# pc_OpenOx-ESP32_v1_1.net
KiCad netlist of a schematic drawn in EAGLE
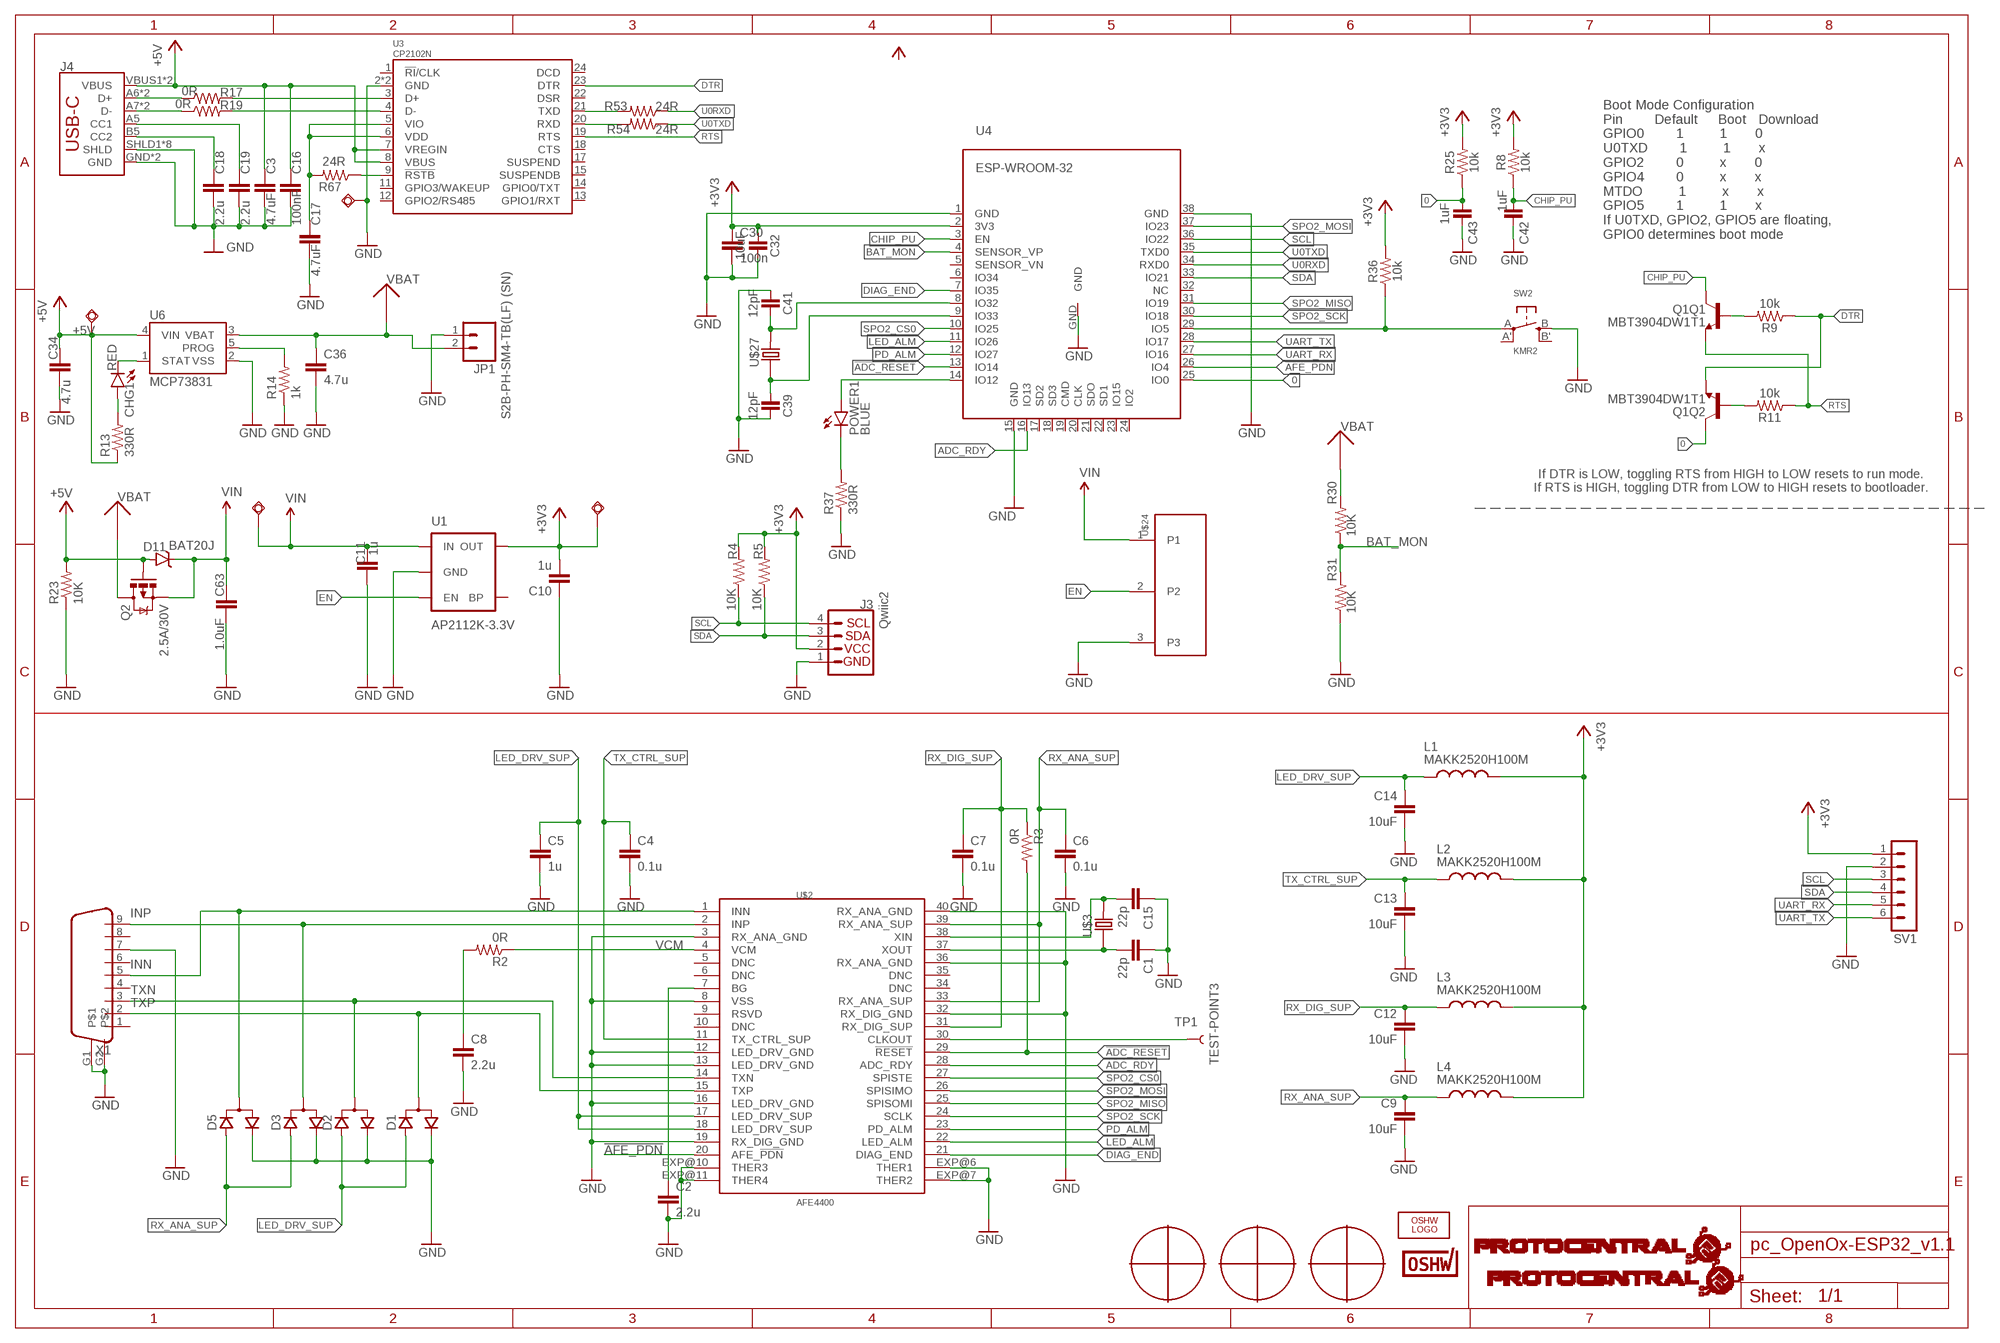
[diagram p0: schematic, sheet 1]

(export (version "E")
  (design (tool "Eeschema 10.0.6"))
  (components
    (comp (ref "C1")
      (value "22p")
      (footprint "eagle-import:C0402")
      (libsource (lib "eagle-import") (part "C-EUC0402"))
    )
    (comp (ref "C2")
      (value "2.2u")
      (footprint "eagle-import:C0402")
      (libsource (lib "eagle-import") (part "C-EUC0402"))
    )
    (comp (ref "C3")
      (value "4.7uF")
      (footprint "eagle-import:C0402")
      (libsource (lib "eagle-import") (part "C-EUC0402"))
    )
    (comp (ref "C4")
      (value "0.1u")
      (footprint "eagle-import:C0805")
      (libsource (lib "eagle-import") (part "C-EUC0805"))
    )
    (comp (ref "C5")
      (value "1u")
      (footprint "eagle-import:C0805")
      (libsource (lib "eagle-import") (part "C-EUC0805"))
    )
    (comp (ref "C6")
      (value "0.1u")
      (footprint "eagle-import:C0805")
      (libsource (lib "eagle-import") (part "C-EUC0805"))
    )
    (comp (ref "C7")
      (value "0.1u")
      (footprint "eagle-import:C0805")
      (libsource (lib "eagle-import") (part "C-EUC0805"))
    )
    (comp (ref "C8")
      (value "2.2u")
      (footprint "eagle-import:C0402")
      (libsource (lib "eagle-import") (part "C-EUC0402"))
    )
    (comp (ref "C9")
      (value "10uF")
      (footprint "eagle-import:C0805")
      (libsource (lib "eagle-import") (part "C-EUC0805"))
    )
    (comp (ref "C10")
      (value "1u")
      (footprint "eagle-import:C0805")
      (libsource (lib "eagle-import") (part "C-EUC0805"))
    )
    (comp (ref "C11")
      (value "1u")
      (footprint "eagle-import:C0805")
      (libsource (lib "eagle-import") (part "C-EUC0805"))
    )
    (comp (ref "C12")
      (value "10uF")
      (footprint "eagle-import:C0805")
      (libsource (lib "eagle-import") (part "C-EUC0805"))
    )
    (comp (ref "C13")
      (value "10uF")
      (footprint "eagle-import:C0805")
      (libsource (lib "eagle-import") (part "C-EUC0805"))
    )
    (comp (ref "C14")
      (value "10uF")
      (footprint "eagle-import:C0805")
      (libsource (lib "eagle-import") (part "C-EUC0805"))
    )
    (comp (ref "C15")
      (value "22p")
      (footprint "eagle-import:C0402")
      (libsource (lib "eagle-import") (part "C-EUC0402"))
    )
    (comp (ref "C16")
      (value "100nF")
      (footprint "eagle-import:C0402")
      (libsource (lib "eagle-import") (part "C-EUC0402"))
    )
    (comp (ref "C17")
      (value "4.7uF")
      (footprint "eagle-import:C0402")
      (libsource (lib "eagle-import") (part "C-EUC0402"))
    )
    (comp (ref "C18")
      (value "2.2u")
      (footprint "eagle-import:C0402")
      (libsource (lib "eagle-import") (part "C-EUC0402"))
    )
    (comp (ref "C19")
      (value "2.2u")
      (footprint "eagle-import:C0402")
      (libsource (lib "eagle-import") (part "C-EUC0402"))
    )
    (comp (ref "C30")
      (value "100n")
      (footprint "eagle-import:C0805")
      (libsource (lib "eagle-import") (part "C-EUC0805"))
    )
    (comp (ref "C32")
      (value "10uF")
      (footprint "eagle-import:C0805")
      (libsource (lib "eagle-import") (part "CAPACITORS-0805"))
    )
    (comp (ref "C34")
      (value "4.7u")
      (footprint "eagle-import:C0805")
      (libsource (lib "eagle-import") (part "C-EUC0805"))
    )
    (comp (ref "C36")
      (value "4.7u")
      (footprint "eagle-import:C0805")
      (libsource (lib "eagle-import") (part "C-EUC0805"))
    )
    (comp (ref "C39")
      (value "12pF")
      (footprint "eagle-import:C0402")
      (libsource (lib "eagle-import") (part "CAPACITORS-0402"))
    )
    (comp (ref "C41")
      (value "12pF")
      (footprint "eagle-import:C0402")
      (libsource (lib "eagle-import") (part "CAPACITORS-0402"))
    )
    (comp (ref "C42")
      (value "1uF")
      (footprint "eagle-import:C0402")
      (libsource (lib "eagle-import") (part "CAPACITORS-0402"))
    )
    (comp (ref "C43")
      (value "1uF")
      (footprint "eagle-import:C0402")
      (libsource (lib "eagle-import") (part "CAPACITORS-0402"))
    )
    (comp (ref "C63")
      (value "1.0uF")
      (footprint "eagle-import:C0402")
      (libsource (lib "eagle-import") (part "C-EUC0402"))
    )
    (comp (ref "CHG1")
      (value "RED")
      (footprint "eagle-import:CHIPLED_0603")
      (libsource (lib "eagle-import") (part "LEDCHIPLED_0603"))
    )
    (comp (ref "D1")
      (value "D_ACACSOT323")
      (footprint "eagle-import:SOT323")
      (libsource (lib "eagle-import") (part "D_ACACSOT323"))
    )
    (comp (ref "D2")
      (value "D_ACACSOT323")
      (footprint "eagle-import:SOT323")
      (libsource (lib "eagle-import") (part "D_ACACSOT323"))
    )
    (comp (ref "D3")
      (value "D_ACACSOT323")
      (footprint "eagle-import:SOT323")
      (libsource (lib "eagle-import") (part "D_ACACSOT323"))
    )
    (comp (ref "D5")
      (value "D_ACACSOT323")
      (footprint "eagle-import:SOT323")
      (libsource (lib "eagle-import") (part "D_ACACSOT323"))
    )
    (comp (ref "D11")
      (value "BAT20J")
      (footprint "eagle-import:SOD-323")
      (libsource (lib "eagle-import") (part "DIODE-SCHOTTKY-BAT20J"))
    )
    (comp (ref "J3")
      (value "Qwiic2")
      (footprint "eagle-import:1X04_1MM_RA")
      (libsource (lib "eagle-import") (part "QWIIC_CONNECTORJS-1MM"))
    )
    (comp (ref "J4")
      (value "USB_C2-LAYER")
      (footprint "eagle-import:USB-C-16P")
      (libsource (lib "eagle-import") (part "USB_C2-LAYER"))
    )
    (comp (ref "JP1")
      (value "S2B-PH-SM4-TB(LF) (SN)")
      (footprint "eagle-import:JST-2-SMD")
      (libsource (lib "eagle-import") (part "M02-JST-2MM-SMT"))
    )
    (comp (ref "L1")
      (value "MAKK2520H100M")
      (footprint "eagle-import:INDC2520X100N")
      (fields (field (name "MF") "Taiyo Yuden"))
      (libsource (lib "eagle-import") (part "MAKK2520H100M"))
    )
    (comp (ref "L2")
      (value "MAKK2520H100M")
      (footprint "eagle-import:INDC2520X100N")
      (fields (field (name "MF") "Taiyo Yuden"))
      (libsource (lib "eagle-import") (part "MAKK2520H100M"))
    )
    (comp (ref "L3")
      (value "MAKK2520H100M")
      (footprint "eagle-import:INDC2520X100N")
      (fields (field (name "MF") "Taiyo Yuden"))
      (libsource (lib "eagle-import") (part "MAKK2520H100M"))
    )
    (comp (ref "L4")
      (value "MAKK2520H100M")
      (footprint "eagle-import:INDC2520X100N")
      (fields (field (name "MF") "Taiyo Yuden"))
      (libsource (lib "eagle-import") (part "MAKK2520H100M"))
    )
    (comp (ref "LOGO2")
      (value "OSHW_LOGO_FILLX0200-NT")
      (footprint "eagle-import:OSHW_FILLX200_NOTEXT")
      (libsource (lib "eagle-import") (part "OSHW_LOGO_FILLX0200-NT"))
    )
    (comp (ref "POWER1")
      (value "BLUE")
      (footprint "eagle-import:CHIPLED_0603")
      (libsource (lib "eagle-import") (part "LEDCHIPLED_0603"))
    )
    (comp (ref "Q1")
      (value "MBT3904DW1T1")
      (footprint "eagle-import:SC70-6")
      (libsource (lib "eagle-import") (part "MBT3904DW1T1"))
    )
    (comp (ref "Q2")
      (value "2.5A/30V")
      (footprint "eagle-import:SOT23-3")
      (libsource (lib "eagle-import") (part "MOSFET-PCHANNELDMG2307L"))
    )
    (comp (ref "R2")
      (value "0R")
      (footprint "eagle-import:R0402")
      (libsource (lib "eagle-import") (part "R-US_R0402"))
    )
    (comp (ref "R3")
      (value "0R")
      (footprint "eagle-import:R0805")
      (libsource (lib "eagle-import") (part "R-US_R0805"))
    )
    (comp (ref "R4")
      (value "10K")
      (footprint "eagle-import:R0402")
      (libsource (lib "eagle-import") (part "R-US_R0402"))
    )
    (comp (ref "R5")
      (value "10K")
      (footprint "eagle-import:R0402")
      (libsource (lib "eagle-import") (part "R-US_R0402"))
    )
    (comp (ref "R8")
      (value "10k")
      (footprint "eagle-import:0603")
      (libsource (lib "eagle-import") (part "10KOHM-1/10W-1%(0603)0603"))
    )
    (comp (ref "R9")
      (value "10k")
      (footprint "eagle-import:0603")
      (libsource (lib "eagle-import") (part "10KOHM-0603-1/10W-1%"))
    )
    (comp (ref "R11")
      (value "10k")
      (footprint "eagle-import:0603")
      (libsource (lib "eagle-import") (part "10KOHM-0603-1/10W-1%"))
    )
    (comp (ref "R13")
      (value "330R")
      (footprint "eagle-import:R0402")
      (libsource (lib "eagle-import") (part "R-US_R0402"))
    )
    (comp (ref "R14")
      (value "1k")
      (footprint "eagle-import:R0402")
      (libsource (lib "eagle-import") (part "R-US_R0402"))
    )
    (comp (ref "R17")
      (value "0R")
      (footprint "eagle-import:R0402")
      (libsource (lib "eagle-import") (part "R-US_R0402"))
    )
    (comp (ref "R19")
      (value "0R")
      (footprint "eagle-import:R0402")
      (libsource (lib "eagle-import") (part "R-US_R0402"))
    )
    (comp (ref "R23")
      (value "10K")
      (footprint "eagle-import:R0402")
      (libsource (lib "eagle-import") (part "R-US_R0402"))
    )
    (comp (ref "R25")
      (value "10k")
      (footprint "eagle-import:0603")
      (libsource (lib "eagle-import") (part "10KOHM-1/10W-1%(0603)0603"))
    )
    (comp (ref "R30")
      (value "10K")
      (footprint "eagle-import:R0402")
      (libsource (lib "eagle-import") (part "R-US_R0402"))
    )
    (comp (ref "R31")
      (value "10K")
      (footprint "eagle-import:R0402")
      (libsource (lib "eagle-import") (part "R-US_R0402"))
    )
    (comp (ref "R36")
      (value "10k")
      (footprint "eagle-import:0603")
      (libsource (lib "eagle-import") (part "10KOHM-1/10W-1%(0603)0603"))
    )
    (comp (ref "R37")
      (value "330R")
      (footprint "eagle-import:R0402")
      (libsource (lib "eagle-import") (part "R-US_R0402"))
    )
    (comp (ref "R53")
      (value "24R")
      (footprint "eagle-import:R0402")
      (libsource (lib "eagle-import") (part "R-US_R0402"))
    )
    (comp (ref "R54")
      (value "24R")
      (footprint "eagle-import:R0402")
      (libsource (lib "eagle-import") (part "R-US_R0402"))
    )
    (comp (ref "R67")
      (value "24R")
      (footprint "eagle-import:R0402")
      (libsource (lib "eagle-import") (part "R-US_R0402"))
    )
    (comp (ref "SV1")
      (value "MA06-1")
      (footprint "eagle-import:MA06-1")
      (libsource (lib "eagle-import") (part "MA06-1"))
    )
    (comp (ref "SW2")
      (value "KMR2")
      (footprint "eagle-import:BTN_KMR2_4.6X2.8")
      (libsource (lib "eagle-import") (part "SWITCH_TACT_SMT4.6X2.8"))
    )
    (comp (ref "SWIO1")
      (value "TPSQTP13R")
      (footprint "eagle-import:TP13R")
      (libsource (lib "eagle-import") (part "TPSQTP13R"))
    )
    (comp (ref "SWIO2")
      (value "TPSQTP13R")
      (footprint "eagle-import:TP13R")
      (libsource (lib "eagle-import") (part "TPSQTP13R"))
    )
    (comp (ref "SWIO3")
      (value "TPSQTP13R")
      (footprint "eagle-import:TP13R")
      (libsource (lib "eagle-import") (part "TPSQTP13R"))
    )
    (comp (ref "SWIO17")
      (value "TPSQTP13R")
      (footprint "eagle-import:TP13R")
      (libsource (lib "eagle-import") (part "TPSQTP13R"))
    )
    (comp (ref "TP1")
      (value "TEST-POINT3")
      (footprint "eagle-import:PAD.03X.03")
      (libsource (lib "eagle-import") (part "TEST-POINT3"))
    )
    (comp (ref "U$2")
      (value "AFE4400")
      (footprint "eagle-import:QFN-40")
      (libsource (lib "eagle-import") (part "AFE4400"))
    )
    (comp (ref "U$3")
      (value "ABM3")
      (footprint "eagle-import:ABM3")
      (libsource (lib "eagle-import") (part "ABM3"))
    )
    (comp (ref "U$4")
      (value "PROTY_LOGO_WITH_TEXT")
      (footprint "eagle-import:PROTY_WITH_TEXT")
      (libsource (lib "eagle-import") (part "PROTY_LOGO_WITH_TEXT"))
    )
    (comp (ref "U$5")
      (value "PROTY-LOGO")
      (footprint "eagle-import:LOGO-PROTY")
      (libsource (lib "eagle-import") (part "PROTY-LOGO"))
    )
    (comp (ref "U$7")
      (value "CERT-SMALL")
      (footprint "eagle-import:CERT-SMALL-SILK")
      (libsource (lib "eagle-import") (part "CERT-SMALL"))
    )
    (comp (ref "U$24")
      (value "JS102011SCQN")
      (footprint "eagle-import:JS102011SCQN")
      (libsource (lib "eagle-import") (part "JS102011SCQN"))
    )
    (comp (ref "U$27")
      (value "520-327-12.5-34B(32.768KHZ)")
      (footprint "eagle-import:ECX-31B")
      (libsource (lib "eagle-import") (part "ECS-X-34B"))
    )
    (comp (ref "U$33")
      (value "FUDCIALPOINTS")
      (footprint "eagle-import:FIDUCIALPOINTS")
      (libsource (lib "eagle-import") (part "FUDCIALPOINTS"))
    )
    (comp (ref "U$34")
      (value "FUDCIALPOINTS")
      (footprint "eagle-import:FIDUCIALPOINTS")
      (libsource (lib "eagle-import") (part "FUDCIALPOINTS"))
    )
    (comp (ref "U$35")
      (value "FUDCIALPOINTS")
      (footprint "eagle-import:FIDUCIALPOINTS")
      (libsource (lib "eagle-import") (part "FUDCIALPOINTS"))
    )
    (comp (ref "U1")
      (value "AP2112K-3.3V")
      (footprint "eagle-import:SOT23-5")
      (libsource (lib "eagle-import") (part "V_REG_LDOSMD"))
    )
    (comp (ref "U3")
      (value "CP2102N")
      (footprint "eagle-import:QFN24")
      (libsource (lib "eagle-import") (part "CP2102N"))
    )
    (comp (ref "U4")
      (value "ESP-WROOM-32")
      (footprint "eagle-import:ESP-WROOM-32")
      (libsource (lib "eagle-import") (part "ESP-WROOM-32"))
    )
    (comp (ref "U6")
      (value "MCP73831")
      (footprint "eagle-import:SOT23-5")
      (libsource (lib "eagle-import") (part "MCP73831"))
    )
    (comp (ref "X1")
      (value "DB9")
      (footprint "eagle-import:DB9")
      (libsource (lib "eagle-import") (part "DB9"))
    )
  )
  (nets
    (net (code "1") (name "+3V3") (class "Default")
      (node (ref "C10") (pin "2") (pinfunction "2_2") (pintype "passive"))
      (node (ref "C30") (pin "1") (pinfunction "1_1") (pintype "passive"))
      (node (ref "C32") (pin "1") (pinfunction "1_1") (pintype "passive"))
      (node (ref "J3") (pin "2") (pinfunction "2_2") (pintype "power_in"))
      (node (ref "L1") (pin "2") (pinfunction "2_2") (pintype "passive"))
      (node (ref "L2") (pin "2") (pinfunction "2_2") (pintype "passive"))
      (node (ref "L3") (pin "2") (pinfunction "2_2") (pintype "passive"))
      (node (ref "L4") (pin "2") (pinfunction "2_2") (pintype "passive"))
      (node (ref "R25") (pin "2") (pinfunction "2_2") (pintype "passive"))
      (node (ref "R36") (pin "2") (pinfunction "2_2") (pintype "passive"))
      (node (ref "R4") (pin "2") (pinfunction "2_2") (pintype "passive"))
      (node (ref "R5") (pin "2") (pinfunction "2_2") (pintype "passive"))
      (node (ref "R8") (pin "2") (pinfunction "2_2") (pintype "passive"))
      (node (ref "SV1") (pin "1") (pinfunction "1_1") (pintype "passive"))
      (node (ref "SWIO1") (pin "TP") (pinfunction "TP_TP") (pintype "input"))
      (node (ref "U1") (pin "5") (pinfunction "OUT_5") (pintype "passive"))
      (node (ref "U4") (pin "2") (pinfunction "3V3_2") (pintype "bidirectional"))
    )
    (net (code "2") (name "+5V") (class "Default")
      (node (ref "C16") (pin "1") (pinfunction "1_1") (pintype "passive"))
      (node (ref "C3") (pin "1") (pinfunction "1_1") (pintype "passive"))
      (node (ref "C34") (pin "1") (pinfunction "1_1") (pintype "passive"))
      (node (ref "D11") (pin "A") (pinfunction "A_A") (pintype "passive"))
      (node (ref "J4") (pin "VBUS1") (pinfunction "VBUS_VBUS1") (pintype "bidirectional"))
      (node (ref "J4") (pin "VBUS2") (pinfunction "VBUS_VBUS2") (pintype "bidirectional"))
      (node (ref "Q2") (pin "1") (pinfunction "G_1") (pintype "passive"))
      (node (ref "R13") (pin "1") (pinfunction "1_1") (pintype "passive"))
      (node (ref "R23") (pin "2") (pinfunction "2_2") (pintype "passive"))
      (node (ref "SWIO3") (pin "TP") (pinfunction "TP_TP") (pintype "input"))
      (node (ref "U3") (pin "7") (pinfunction "VREGIN_7") (pintype "bidirectional"))
      (node (ref "U3") (pin "8") (pinfunction "VBUS_8") (pintype "bidirectional"))
      (node (ref "U6") (pin "4") (pinfunction "VIN_4") (pintype "power_in"))
    )
    (net (code "3") (name "/INN") (class "Default")
      (node (ref "D5") (pin "1") (pinfunction "CA_1") (pintype "passive"))
      (node (ref "U$2") (pin "1") (pinfunction "INN_1") (pintype "bidirectional"))
      (node (ref "X1") (pin "5") (pinfunction "5_5") (pintype "passive"))
    )
    (net (code "4") (name "/INP") (class "Default")
      (node (ref "D3") (pin "1") (pinfunction "CA_1") (pintype "passive"))
      (node (ref "U$2") (pin "2") (pinfunction "INP_2") (pintype "bidirectional"))
      (node (ref "X1") (pin "9") (pinfunction "9_9") (pintype "passive"))
    )
    (net (code "5") (name "/TXN") (class "Default")
      (node (ref "D2") (pin "1") (pinfunction "CA_1") (pintype "passive"))
      (node (ref "U$2") (pin "14") (pinfunction "TXN_14") (pintype "bidirectional"))
      (node (ref "X1") (pin "3") (pinfunction "3_3") (pintype "passive"))
    )
    (net (code "6") (name "/TXP") (class "Default")
      (node (ref "D1") (pin "1") (pinfunction "CA_1") (pintype "passive"))
      (node (ref "U$2") (pin "15") (pinfunction "TXP_15") (pintype "bidirectional"))
      (node (ref "X1") (pin "2") (pinfunction "2_2") (pintype "passive"))
    )
    (net (code "7") (name "/VCM") (class "Default")
      (node (ref "R2") (pin "1") (pinfunction "1_1") (pintype "passive"))
      (node (ref "U$2") (pin "4") (pinfunction "VCM_4") (pintype "bidirectional"))
    )
    (net (code "8") (name "/~{ADC_RESET}") (class "Default")
      (node (ref "R3") (pin "2") (pinfunction "2_2") (pintype "passive"))
      (node (ref "U$2") (pin "29") (pinfunction "~{RESET}_29") (pintype "bidirectional"))
      (node (ref "U4") (pin "13") (pinfunction "IO14_13") (pintype "bidirectional"))
    )
    (net (code "9") (name "/~{AFE_PDN}") (class "Default")
      (node (ref "U$2") (pin "20") (pinfunction "AFE_~{PDN}_20") (pintype "bidirectional"))
      (node (ref "U4") (pin "26") (pinfunction "IO4_26") (pintype "bidirectional"))
    )
    (net (code "10") (name "0") (class "Default")
      (node (ref "C43") (pin "1") (pinfunction "1_1") (pintype "passive"))
      (node (ref "Q1") (pin "6") (pinfunction "C_6") (pintype "passive"))
      (node (ref "R25") (pin "1") (pinfunction "1_1") (pintype "passive"))
      (node (ref "U4") (pin "25") (pinfunction "IO0_25") (pintype "bidirectional"))
    )
    (net (code "11") (name "ADC_RDY") (class "Default")
      (node (ref "U$2") (pin "28") (pinfunction "ADC_RDY_28") (pintype "bidirectional"))
      (node (ref "U4") (pin "16") (pinfunction "IO13_16") (pintype "bidirectional"))
    )
    (net (code "12") (name "BAT_MON") (class "Default")
      (node (ref "R30") (pin "1") (pinfunction "1_1") (pintype "passive"))
      (node (ref "R31") (pin "2") (pinfunction "2_2") (pintype "passive"))
      (node (ref "U4") (pin "4") (pinfunction "SENSOR_VP_4") (pintype "bidirectional"))
    )
    (net (code "13") (name "CHIP_PU") (class "Default")
      (node (ref "C42") (pin "1") (pinfunction "1_1") (pintype "passive"))
      (node (ref "Q1") (pin "3") (pinfunction "C_3") (pintype "passive"))
      (node (ref "R8") (pin "1") (pinfunction "1_1") (pintype "passive"))
      (node (ref "U4") (pin "3") (pinfunction "EN_3") (pintype "bidirectional"))
    )
    (net (code "14") (name "DIAG_END") (class "Default")
      (node (ref "U$2") (pin "21") (pinfunction "DIAG_END_21") (pintype "bidirectional"))
      (node (ref "U4") (pin "7") (pinfunction "IO35_7") (pintype "bidirectional"))
    )
    (net (code "15") (name "DTR") (class "Default")
      (node (ref "Q1") (pin "1") (pinfunction "E_1") (pintype "passive"))
      (node (ref "R9") (pin "1") (pinfunction "1_1") (pintype "passive"))
      (node (ref "U3") (pin "23") (pinfunction "DTR_23") (pintype "bidirectional"))
    )
    (net (code "16") (name "EN") (class "Default")
      (node (ref "U$24") (pin "2") (pinfunction "P2_2") (pintype "bidirectional"))
      (node (ref "U1") (pin "3") (pinfunction "EN_3") (pintype "input"))
    )
    (net (code "17") (name "GND") (class "Default")
      (node (ref "C1") (pin "1") (pinfunction "1_1") (pintype "passive"))
      (node (ref "C10") (pin "1") (pinfunction "1_1") (pintype "passive"))
      (node (ref "C11") (pin "1") (pinfunction "1_1") (pintype "passive"))
      (node (ref "C12") (pin "2") (pinfunction "2_2") (pintype "passive"))
      (node (ref "C13") (pin "2") (pinfunction "2_2") (pintype "passive"))
      (node (ref "C14") (pin "2") (pinfunction "2_2") (pintype "passive"))
      (node (ref "C15") (pin "1") (pinfunction "1_1") (pintype "passive"))
      (node (ref "C16") (pin "2") (pinfunction "2_2") (pintype "passive"))
      (node (ref "C17") (pin "2") (pinfunction "2_2") (pintype "passive"))
      (node (ref "C18") (pin "2") (pinfunction "2_2") (pintype "passive"))
      (node (ref "C19") (pin "2") (pinfunction "2_2") (pintype "passive"))
      (node (ref "C2") (pin "2") (pinfunction "2_2") (pintype "passive"))
      (node (ref "C3") (pin "2") (pinfunction "2_2") (pintype "passive"))
      (node (ref "C30") (pin "2") (pinfunction "2_2") (pintype "passive"))
      (node (ref "C32") (pin "2") (pinfunction "2_2") (pintype "passive"))
      (node (ref "C34") (pin "2") (pinfunction "2_2") (pintype "passive"))
      (node (ref "C36") (pin "2") (pinfunction "2_2") (pintype "passive"))
      (node (ref "C39") (pin "2") (pinfunction "2_2") (pintype "passive"))
      (node (ref "C4") (pin "2") (pinfunction "2_2") (pintype "passive"))
      (node (ref "C41") (pin "1") (pinfunction "1_1") (pintype "passive"))
      (node (ref "C42") (pin "2") (pinfunction "2_2") (pintype "passive"))
      (node (ref "C43") (pin "2") (pinfunction "2_2") (pintype "passive"))
      (node (ref "C5") (pin "2") (pinfunction "2_2") (pintype "passive"))
      (node (ref "C6") (pin "2") (pinfunction "2_2") (pintype "passive"))
      (node (ref "C63") (pin "2") (pinfunction "2_2") (pintype "passive"))
      (node (ref "C7") (pin "2") (pinfunction "2_2") (pintype "passive"))
      (node (ref "C8") (pin "2") (pinfunction "2_2") (pintype "passive"))
      (node (ref "C9") (pin "2") (pinfunction "2_2") (pintype "passive"))
      (node (ref "D1") (pin "2") (pinfunction "C_2") (pintype "passive"))
      (node (ref "D2") (pin "2") (pinfunction "C_2") (pintype "passive"))
      (node (ref "D3") (pin "2") (pinfunction "C_2") (pintype "passive"))
      (node (ref "D5") (pin "2") (pinfunction "C_2") (pintype "passive"))
      (node (ref "J3") (pin "1") (pinfunction "1_1") (pintype "power_in"))
      (node (ref "J4") (pin "GND") (pinfunction "GND_GND") (pintype "bidirectional"))
      (node (ref "J4") (pin "GND2") (pinfunction "GND_GND2") (pintype "bidirectional"))
      (node (ref "J4") (pin "SHLD1") (pinfunction "SHLD_SHLD1") (pintype "bidirectional"))
      (node (ref "J4") (pin "SHLD2") (pinfunction "SHLD_SHLD2") (pintype "bidirectional"))
      (node (ref "J4") (pin "SHLD3") (pinfunction "SHLD_SHLD3") (pintype "bidirectional"))
      (node (ref "J4") (pin "SHLD4") (pinfunction "SHLD_SHLD4") (pintype "bidirectional"))
      (node (ref "J4") (pin "SHLD5") (pinfunction "SHLD_SHLD5") (pintype "bidirectional"))
      (node (ref "J4") (pin "SHLD6") (pinfunction "SHLD_SHLD6") (pintype "bidirectional"))
      (node (ref "J4") (pin "SHLD7") (pinfunction "SHLD_SHLD7") (pintype "bidirectional"))
      (node (ref "J4") (pin "SHLD8") (pinfunction "SHLD_SHLD8") (pintype "bidirectional"))
      (node (ref "JP1") (pin "1") (pinfunction "1_1") (pintype "passive"))
      (node (ref "R14") (pin "1") (pinfunction "1_1") (pintype "passive"))
      (node (ref "R23") (pin "1") (pinfunction "1_1") (pintype "passive"))
      (node (ref "R31") (pin "1") (pinfunction "1_1") (pintype "passive"))
      (node (ref "R37") (pin "1") (pinfunction "1_1") (pintype "passive"))
      (node (ref "SV1") (pin "2") (pinfunction "2_2") (pintype "passive"))
      (node (ref "SW2") (pin "B") (pinfunction "S_B") (pintype "passive"))
      (node (ref "SWIO17") (pin "TP") (pinfunction "TP_TP") (pintype "input"))
      (node (ref "U$2") (pin "12") (pinfunction "LED_DRV_GND_12") (pintype "bidirectional"))
      (node (ref "U$2") (pin "13") (pinfunction "LED_DRV_GND_13") (pintype "bidirectional"))
      (node (ref "U$2") (pin "16") (pinfunction "LED_DRV_GND_16") (pintype "bidirectional"))
      (node (ref "U$2") (pin "19") (pinfunction "RX_DIG_GND_19") (pintype "bidirectional"))
      (node (ref "U$2") (pin "3") (pinfunction "RX_ANA_GND_3") (pintype "bidirectional"))
      (node (ref "U$2") (pin "32") (pinfunction "RX_DIG_GND_32") (pintype "bidirectional"))
      (node (ref "U$2") (pin "36") (pinfunction "RX_ANA_GND_36") (pintype "bidirectional"))
      (node (ref "U$2") (pin "40") (pinfunction "RX_ANA_GND_40") (pintype "bidirectional"))
      (node (ref "U$2") (pin "8") (pinfunction "VSS_8") (pintype "bidirectional"))
      (node (ref "U$2") (pin "EXP@10") (pinfunction "THER3_EXP@10") (pintype "bidirectional"))
      (node (ref "U$2") (pin "EXP@11") (pinfunction "THER4_EXP@11") (pintype "bidirectional"))
      (node (ref "U$2") (pin "EXP@6") (pinfunction "THER1_EXP@6") (pintype "bidirectional"))
      (node (ref "U$2") (pin "EXP@7") (pinfunction "THER2_EXP@7") (pintype "bidirectional"))
      (node (ref "U$24") (pin "3") (pinfunction "P3_3") (pintype "bidirectional"))
      (node (ref "U1") (pin "2") (pinfunction "GND_2") (pintype "input"))
      (node (ref "U3") (pin "2") (pinfunction "GND_2") (pintype "bidirectional"))
      (node (ref "U3") (pin "PAD") (pinfunction "GND_PAD") (pintype "bidirectional"))
      (node (ref "U4") (pin "1") (pinfunction "GND_1") (pintype "bidirectional"))
      (node (ref "U4") (pin "15") (pinfunction "GND_15") (pintype "bidirectional"))
      (node (ref "U4") (pin "38") (pinfunction "GND_38") (pintype "bidirectional"))
      (node (ref "U4") (pin "GND") (pinfunction "GND_GND") (pintype "bidirectional"))
      (node (ref "U6") (pin "2") (pinfunction "VSS_2") (pintype "power_in"))
      (node (ref "X1") (pin "7") (pinfunction "7_7") (pintype "passive"))
      (node (ref "X1") (pin "G1") (pinfunction "P$1_G1") (pintype "bidirectional"))
      (node (ref "X1") (pin "G2") (pinfunction "P$2_G2") (pintype "bidirectional"))
    )
    (net (code "18") (name "LED_ALM") (class "Default")
      (node (ref "U$2") (pin "22") (pinfunction "LED_ALM_22") (pintype "bidirectional"))
      (node (ref "U4") (pin "11") (pinfunction "IO26_11") (pintype "bidirectional"))
    )
    (net (code "19") (name "LED_DRV_SUP") (class "Default")
      (node (ref "C14") (pin "1") (pinfunction "1_1") (pintype "passive"))
      (node (ref "C5") (pin "1") (pinfunction "1_1") (pintype "passive"))
      (node (ref "D1") (pin "3") (pinfunction "A_3") (pintype "passive"))
      (node (ref "D2") (pin "3") (pinfunction "A_3") (pintype "passive"))
      (node (ref "L1") (pin "1") (pinfunction "1_1") (pintype "passive"))
      (node (ref "U$2") (pin "17") (pinfunction "LED_DRV_SUP_17") (pintype "bidirectional"))
      (node (ref "U$2") (pin "18") (pinfunction "LED_DRV_SUP_18") (pintype "bidirectional"))
    )
    (net (code "20") (name "Net-(C8-Pad1)") (class "Default")
      (node (ref "C8") (pin "1") (pinfunction "1_1") (pintype "passive"))
      (node (ref "R2") (pin "2") (pinfunction "2_2") (pintype "passive"))
    )
    (net (code "21") (name "Net-(CHG1-PadA)") (class "Default")
      (node (ref "CHG1") (pin "A") (pinfunction "A_A") (pintype "passive"))
      (node (ref "R13") (pin "2") (pinfunction "2_2") (pintype "passive"))
    )
    (net (code "22") (name "Net-(J4-CC1)") (class "Default")
      (node (ref "C19") (pin "1") (pinfunction "1_1") (pintype "passive"))
      (node (ref "J4") (pin "A5") (pinfunction "CC1_A5") (pintype "bidirectional"))
    )
    (net (code "23") (name "Net-(J4-CC2)") (class "Default")
      (node (ref "C18") (pin "1") (pinfunction "1_1") (pintype "passive"))
      (node (ref "J4") (pin "B5") (pinfunction "CC2_B5") (pintype "bidirectional"))
    )
    (net (code "24") (name "Net-(J4-D+-PadA6)") (class "Default")
      (node (ref "J4") (pin "A6") (pinfunction "D+_A6") (pintype "bidirectional"))
      (node (ref "J4") (pin "B6") (pinfunction "D+_B6") (pintype "bidirectional"))
      (node (ref "R17") (pin "1") (pinfunction "1_1") (pintype "passive"))
    )
    (net (code "25") (name "Net-(J4-D--PadA7)") (class "Default")
      (node (ref "J4") (pin "A7") (pinfunction "D-_A7") (pintype "bidirectional"))
      (node (ref "J4") (pin "B7") (pinfunction "D-_B7") (pintype "bidirectional"))
      (node (ref "R19") (pin "1") (pinfunction "1_1") (pintype "passive"))
    )
    (net (code "26") (name "Net-(POWER1-PadC)") (class "Default")
      (node (ref "POWER1") (pin "C") (pinfunction "C_C") (pintype "passive"))
      (node (ref "R37") (pin "2") (pinfunction "2_2") (pintype "passive"))
    )
    (net (code "27") (name "Net-(Q1A-B)") (class "Default")
      (node (ref "Q1") (pin "5") (pinfunction "B_5") (pintype "passive"))
      (node (ref "R9") (pin "2") (pinfunction "2_2") (pintype "passive"))
    )
    (net (code "28") (name "Net-(Q1B-B)") (class "Default")
      (node (ref "Q1") (pin "2") (pinfunction "B_2") (pintype "passive"))
      (node (ref "R11") (pin "2") (pinfunction "2_2") (pintype "passive"))
    )
    (net (code "29") (name "Net-(SW2-P)") (class "Default")
      (node (ref "R36") (pin "1") (pinfunction "1_1") (pintype "passive"))
      (node (ref "SW2") (pin "A") (pinfunction "P_A") (pintype "passive"))
      (node (ref "U4") (pin "29") (pinfunction "IO5_29") (pintype "bidirectional"))
    )
    (net (code "30") (name "Net-(TP1-1)") (class "Default")
      (node (ref "TP1") (pin "P$1") (pinfunction "1_P$1") (pintype "bidirectional"))
      (node (ref "U$2") (pin "30") (pinfunction "CLKOUT_30") (pintype "bidirectional"))
    )
    (net (code "31") (name "Net-(U$2-BG)") (class "Default")
      (node (ref "C2") (pin "1") (pinfunction "1_1") (pintype "passive"))
      (node (ref "U$2") (pin "7") (pinfunction "BG_7") (pintype "bidirectional"))
    )
    (net (code "32") (name "Net-(U$2-XIN)") (class "Default")
      (node (ref "C15") (pin "2") (pinfunction "2_2") (pintype "passive"))
      (node (ref "U$2") (pin "38") (pinfunction "XIN_38") (pintype "bidirectional"))
      (node (ref "U$3") (pin "2") (pinfunction "2_2") (pintype "passive"))
    )
    (net (code "33") (name "Net-(U$2-XOUT)") (class "Default")
      (node (ref "C1") (pin "2") (pinfunction "2_2") (pintype "passive"))
      (node (ref "U$2") (pin "37") (pinfunction "XOUT_37") (pintype "bidirectional"))
      (node (ref "U$3") (pin "1") (pinfunction "1_1") (pintype "passive"))
    )
    (net (code "34") (name "Net-(U$27-1)") (class "Default")
      (node (ref "C39") (pin "1") (pinfunction "1_1") (pintype "passive"))
      (node (ref "U$27") (pin "P$1") (pinfunction "1_P$1") (pintype "passive"))
      (node (ref "U4") (pin "9") (pinfunction "IO33_9") (pintype "bidirectional"))
    )
    (net (code "35") (name "Net-(U$27-2)") (class "Default")
      (node (ref "C41") (pin "2") (pinfunction "2_2") (pintype "passive"))
      (node (ref "U$27") (pin "P$2") (pinfunction "2_P$2") (pintype "passive"))
      (node (ref "U4") (pin "8") (pinfunction "IO32_8") (pintype "bidirectional"))
    )
    (net (code "36") (name "Net-(U3-D+)") (class "Default")
      (node (ref "R17") (pin "2") (pinfunction "2_2") (pintype "passive"))
      (node (ref "U3") (pin "3") (pinfunction "D+_3") (pintype "bidirectional"))
    )
    (net (code "37") (name "Net-(U3-D-)") (class "Default")
      (node (ref "R19") (pin "2") (pinfunction "2_2") (pintype "passive"))
      (node (ref "U3") (pin "4") (pinfunction "D-_4") (pintype "bidirectional"))
    )
    (net (code "38") (name "Net-(U3-RXD)") (class "Default")
      (node (ref "R54") (pin "2") (pinfunction "2_2") (pintype "passive"))
      (node (ref "U3") (pin "20") (pinfunction "RXD_20") (pintype "bidirectional"))
    )
    (net (code "39") (name "Net-(U3-TXD)") (class "Default")
      (node (ref "R53") (pin "2") (pinfunction "2_2") (pintype "passive"))
      (node (ref "U3") (pin "21") (pinfunction "TXD_21") (pintype "bidirectional"))
    )
    (net (code "40") (name "Net-(U3-VDD)") (class "Default")
      (node (ref "C17") (pin "1") (pinfunction "1_1") (pintype "passive"))
      (node (ref "R67") (pin "2") (pinfunction "2_2") (pintype "passive"))
      (node (ref "U3") (pin "5") (pinfunction "VIO_5") (pintype "bidirectional"))
      (node (ref "U3") (pin "6") (pinfunction "VDD_6") (pintype "bidirectional"))
    )
    (net (code "41") (name "Net-(U3-~{RSTB})") (class "Default")
      (node (ref "R67") (pin "1") (pinfunction "1_1") (pintype "passive"))
      (node (ref "U3") (pin "9") (pinfunction "~{RSTB}_9") (pintype "bidirectional"))
    )
    (net (code "42") (name "Net-(U4-IO12)") (class "Default")
      (node (ref "POWER1") (pin "A") (pinfunction "A_A") (pintype "passive"))
      (node (ref "U4") (pin "14") (pinfunction "IO12_14") (pintype "bidirectional"))
    )
    (net (code "43") (name "Net-(U6-PROG)") (class "Default")
      (node (ref "R14") (pin "2") (pinfunction "2_2") (pintype "passive"))
      (node (ref "U6") (pin "5") (pinfunction "PROG_5") (pintype "input"))
    )
    (net (code "44") (name "Net-(U6-STAT)") (class "Default")
      (node (ref "CHG1") (pin "C") (pinfunction "C_C") (pintype "passive"))
      (node (ref "U6") (pin "1") (pinfunction "STAT_1") (pintype "output"))
    )
    (net (code "45") (name "PD_ALM") (class "Default")
      (node (ref "U$2") (pin "23") (pinfunction "PD_ALM_23") (pintype "bidirectional"))
      (node (ref "U4") (pin "12") (pinfunction "IO27_12") (pintype "bidirectional"))
    )
    (net (code "46") (name "RTS") (class "Default")
      (node (ref "Q1") (pin "4") (pinfunction "E_4") (pintype "passive"))
      (node (ref "R11") (pin "1") (pinfunction "1_1") (pintype "passive"))
      (node (ref "U3") (pin "19") (pinfunction "RTS_19") (pintype "bidirectional"))
    )
    (net (code "47") (name "RX_ANA_SUP") (class "Default")
      (node (ref "C6") (pin "1") (pinfunction "1_1") (pintype "passive"))
      (node (ref "C9") (pin "1") (pinfunction "1_1") (pintype "passive"))
      (node (ref "D3") (pin "3") (pinfunction "A_3") (pintype "passive"))
      (node (ref "D5") (pin "3") (pinfunction "A_3") (pintype "passive"))
      (node (ref "L4") (pin "1") (pinfunction "1_1") (pintype "passive"))
      (node (ref "U$2") (pin "33") (pinfunction "RX_ANA_SUP_33") (pintype "bidirectional"))
      (node (ref "U$2") (pin "39") (pinfunction "RX_ANA_SUP_39") (pintype "bidirectional"))
    )
    (net (code "48") (name "RX_DIG_SUP") (class "Default")
      (node (ref "C12") (pin "1") (pinfunction "1_1") (pintype "passive"))
      (node (ref "C7") (pin "1") (pinfunction "1_1") (pintype "passive"))
      (node (ref "L3") (pin "1") (pinfunction "1_1") (pintype "passive"))
      (node (ref "R3") (pin "1") (pinfunction "1_1") (pintype "passive"))
      (node (ref "U$2") (pin "31") (pinfunction "RX_DIG_SUP_31") (pintype "bidirectional"))
    )
    (net (code "49") (name "SCL") (class "Default")
      (node (ref "J3") (pin "4") (pinfunction "4_4") (pintype "passive"))
      (node (ref "R4") (pin "1") (pinfunction "1_1") (pintype "passive"))
      (node (ref "SV1") (pin "3") (pinfunction "3_3") (pintype "passive"))
      (node (ref "U4") (pin "36") (pinfunction "IO22_36") (pintype "bidirectional"))
    )
    (net (code "50") (name "SDA") (class "Default")
      (node (ref "J3") (pin "3") (pinfunction "3_3") (pintype "passive"))
      (node (ref "R5") (pin "1") (pinfunction "1_1") (pintype "passive"))
      (node (ref "SV1") (pin "4") (pinfunction "4_4") (pintype "passive"))
      (node (ref "U4") (pin "33") (pinfunction "IO21_33") (pintype "bidirectional"))
    )
    (net (code "51") (name "SPO2_CS0") (class "Default")
      (node (ref "U$2") (pin "27") (pinfunction "SPISTE_27") (pintype "bidirectional"))
      (node (ref "U4") (pin "10") (pinfunction "IO25_10") (pintype "bidirectional"))
    )
    (net (code "52") (name "SPO2_MISO") (class "Default")
      (node (ref "U$2") (pin "25") (pinfunction "SPISOMI_25") (pintype "bidirectional"))
      (node (ref "U4") (pin "31") (pinfunction "IO19_31") (pintype "bidirectional"))
    )
    (net (code "53") (name "SPO2_MOSI") (class "Default")
      (node (ref "U$2") (pin "26") (pinfunction "SPISIMO_26") (pintype "bidirectional"))
      (node (ref "U4") (pin "37") (pinfunction "IO23_37") (pintype "bidirectional"))
    )
    (net (code "54") (name "SPO2_SCK") (class "Default")
      (node (ref "U$2") (pin "24") (pinfunction "SCLK_24") (pintype "bidirectional"))
      (node (ref "U4") (pin "30") (pinfunction "IO18_30") (pintype "bidirectional"))
    )
    (net (code "55") (name "TX_CTRL_SUP") (class "Default")
      (node (ref "C13") (pin "1") (pinfunction "1_1") (pintype "passive"))
      (node (ref "C4") (pin "1") (pinfunction "1_1") (pintype "passive"))
      (node (ref "L2") (pin "1") (pinfunction "1_1") (pintype "passive"))
      (node (ref "U$2") (pin "11") (pinfunction "TX_CTRL_SUP_11") (pintype "bidirectional"))
    )
    (net (code "56") (name "U0RXD") (class "Default")
      (node (ref "R53") (pin "1") (pinfunction "1_1") (pintype "passive"))
      (node (ref "U4") (pin "34") (pinfunction "RXD0_34") (pintype "bidirectional"))
    )
    (net (code "57") (name "U0TXD") (class "Default")
      (node (ref "R54") (pin "1") (pinfunction "1_1") (pintype "passive"))
      (node (ref "U4") (pin "35") (pinfunction "TXD0_35") (pintype "bidirectional"))
    )
    (net (code "58") (name "UART_RX") (class "Default")
      (node (ref "SV1") (pin "5") (pinfunction "5_5") (pintype "passive"))
      (node (ref "U4") (pin "27") (pinfunction "IO16_27") (pintype "bidirectional"))
    )
    (net (code "59") (name "UART_TX") (class "Default")
      (node (ref "SV1") (pin "6") (pinfunction "6_6") (pintype "passive"))
      (node (ref "U4") (pin "28") (pinfunction "IO17_28") (pintype "bidirectional"))
    )
    (net (code "60") (name "VBAT") (class "Default")
      (node (ref "C36") (pin "1") (pinfunction "1_1") (pintype "passive"))
      (node (ref "JP1") (pin "2") (pinfunction "2_2") (pintype "passive"))
      (node (ref "Q2") (pin "3") (pinfunction "D_3") (pintype "passive"))
      (node (ref "R30") (pin "2") (pinfunction "2_2") (pintype "passive"))
      (node (ref "U6") (pin "3") (pinfunction "VBAT_3") (pintype "power_in"))
    )
    (net (code "61") (name "VIN") (class "Default")
      (node (ref "C11") (pin "2") (pinfunction "2_2") (pintype "passive"))
      (node (ref "C63") (pin "1") (pinfunction "1_1") (pintype "passive"))
      (node (ref "D11") (pin "C") (pinfunction "C_C") (pintype "passive"))
      (node (ref "Q2") (pin "2") (pinfunction "S_2") (pintype "passive"))
      (node (ref "SWIO2") (pin "TP") (pinfunction "TP_TP") (pintype "input"))
      (node (ref "U$24") (pin "1") (pinfunction "P1_1") (pintype "bidirectional"))
      (node (ref "U1") (pin "1") (pinfunction "IN_1") (pintype "input"))
    )
    (net (code "62") (name "unconnected-(SW2-P1-PadA')") (class "Default")
      (node (ref "SW2") (pin "A'") (pinfunction "P1_A'") (pintype "passive"))
    )
    (net (code "63") (name "unconnected-(SW2-S1-PadB')") (class "Default")
      (node (ref "SW2") (pin "B'") (pinfunction "S1_B'") (pintype "passive"))
    )
    (net (code "64") (name "unconnected-(U$2-DNC-Pad5)") (class "Default")
      (node (ref "U$2") (pin "5") (pinfunction "DNC_5") (pintype "bidirectional"))
    )
    (net (code "65") (name "unconnected-(U$2-DNC-Pad6)") (class "Default")
      (node (ref "U$2") (pin "6") (pinfunction "DNC_6") (pintype "bidirectional"))
    )
    (net (code "66") (name "unconnected-(U$2-DNC-Pad10)") (class "Default")
      (node (ref "U$2") (pin "10") (pinfunction "DNC_10") (pintype "bidirectional"))
    )
    (net (code "67") (name "unconnected-(U$2-DNC-Pad34)") (class "Default")
      (node (ref "U$2") (pin "34") (pinfunction "DNC_34") (pintype "bidirectional"))
    )
    (net (code "68") (name "unconnected-(U$2-DNC-Pad35)") (class "Default")
      (node (ref "U$2") (pin "35") (pinfunction "DNC_35") (pintype "bidirectional"))
    )
    (net (code "69") (name "unconnected-(U$2-RSVD-Pad9)") (class "Default")
      (node (ref "U$2") (pin "9") (pinfunction "RSVD_9") (pintype "bidirectional"))
    )
    (net (code "70") (name "unconnected-(U1-BP-Pad4)") (class "Default")
      (node (ref "U1") (pin "4") (pinfunction "BP_4") (pintype "input"))
    )
    (net (code "71") (name "unconnected-(U3-CTS-Pad18)") (class "Default")
      (node (ref "U3") (pin "18") (pinfunction "CTS_18") (pintype "bidirectional"))
    )
    (net (code "72") (name "unconnected-(U3-DCD-Pad24)") (class "Default")
      (node (ref "U3") (pin "24") (pinfunction "DCD_24") (pintype "bidirectional"))
    )
    (net (code "73") (name "unconnected-(U3-DSR-Pad22)") (class "Default")
      (node (ref "U3") (pin "22") (pinfunction "DSR_22") (pintype "bidirectional"))
    )
    (net (code "74") (name "unconnected-(U3-GPIO0{slash}TXT-Pad14)") (class "Default")
      (node (ref "U3") (pin "14") (pinfunction "GPIO0/TXT_14") (pintype "bidirectional"))
    )
    (net (code "75") (name "unconnected-(U3-GPIO1{slash}RXT-Pad13)") (class "Default")
      (node (ref "U3") (pin "13") (pinfunction "GPIO1/RXT_13") (pintype "bidirectional"))
    )
    (net (code "76") (name "unconnected-(U3-GPIO2{slash}RS485-Pad12)") (class "Default")
      (node (ref "U3") (pin "12") (pinfunction "GPIO2/RS485_12") (pintype "bidirectional"))
    )
    (net (code "77") (name "unconnected-(U3-GPIO3{slash}WAKEUP-Pad11)") (class "Default")
      (node (ref "U3") (pin "11") (pinfunction "GPIO3/WAKEUP_11") (pintype "bidirectional"))
    )
    (net (code "78") (name "unconnected-(U3-SUSPEND-Pad17)") (class "Default")
      (node (ref "U3") (pin "17") (pinfunction "SUSPEND_17") (pintype "bidirectional"))
    )
    (net (code "79") (name "unconnected-(U3-SUSPENDB-Pad15)") (class "Default")
      (node (ref "U3") (pin "15") (pinfunction "SUSPENDB_15") (pintype "bidirectional"))
    )
    (net (code "80") (name "unconnected-(U3-~{RI}{slash}CLK-Pad1)") (class "Default")
      (node (ref "U3") (pin "1") (pinfunction "~{RI}/CLK_1") (pintype "bidirectional"))
    )
    (net (code "81") (name "unconnected-(U4-CLK-Pad20)") (class "Default")
      (node (ref "U4") (pin "20") (pinfunction "CLK_20") (pintype "bidirectional"))
    )
    (net (code "82") (name "unconnected-(U4-CMD-Pad19)") (class "Default")
      (node (ref "U4") (pin "19") (pinfunction "CMD_19") (pintype "bidirectional"))
    )
    (net (code "83") (name "unconnected-(U4-IO2-Pad24)") (class "Default")
      (node (ref "U4") (pin "24") (pinfunction "IO2_24") (pintype "bidirectional"))
    )
    (net (code "84") (name "unconnected-(U4-IO15-Pad23)") (class "Default")
      (node (ref "U4") (pin "23") (pinfunction "IO15_23") (pintype "bidirectional"))
    )
    (net (code "85") (name "unconnected-(U4-IO34-Pad6)") (class "Default")
      (node (ref "U4") (pin "6") (pinfunction "IO34_6") (pintype "bidirectional"))
    )
    (net (code "86") (name "unconnected-(U4-NC-Pad32)") (class "Default")
      (node (ref "U4") (pin "32") (pinfunction "NC_32") (pintype "bidirectional"))
    )
    (net (code "87") (name "unconnected-(U4-SD1-Pad22)") (class "Default")
      (node (ref "U4") (pin "22") (pinfunction "SD1_22") (pintype "bidirectional"))
    )
    (net (code "88") (name "unconnected-(U4-SD2-Pad17)") (class "Default")
      (node (ref "U4") (pin "17") (pinfunction "SD2_17") (pintype "bidirectional"))
    )
    (net (code "89") (name "unconnected-(U4-SD3-Pad18)") (class "Default")
      (node (ref "U4") (pin "18") (pinfunction "SD3_18") (pintype "bidirectional"))
    )
    (net (code "90") (name "unconnected-(U4-SDO-Pad21)") (class "Default")
      (node (ref "U4") (pin "21") (pinfunction "SDO_21") (pintype "bidirectional"))
    )
    (net (code "91") (name "unconnected-(U4-SENSOR_VN-Pad5)") (class "Default")
      (node (ref "U4") (pin "5") (pinfunction "SENSOR_VN_5") (pintype "bidirectional"))
    )
    (net (code "92") (name "unconnected-(X1-Pad1)") (class "Default")
      (node (ref "X1") (pin "1") (pinfunction "1_1") (pintype "passive"))
    )
    (net (code "93") (name "unconnected-(X1-Pad4)") (class "Default")
      (node (ref "X1") (pin "4") (pinfunction "4_4") (pintype "passive"))
    )
    (net (code "94") (name "unconnected-(X1-Pad6)") (class "Default")
      (node (ref "X1") (pin "6") (pinfunction "6_6") (pintype "passive"))
    )
    (net (code "95") (name "unconnected-(X1-Pad8)") (class "Default")
      (node (ref "X1") (pin "8") (pinfunction "8_8") (pintype "passive"))
    )
  )
)
